# detector.net
KiCad netlist of a schematic drawn in EAGLE
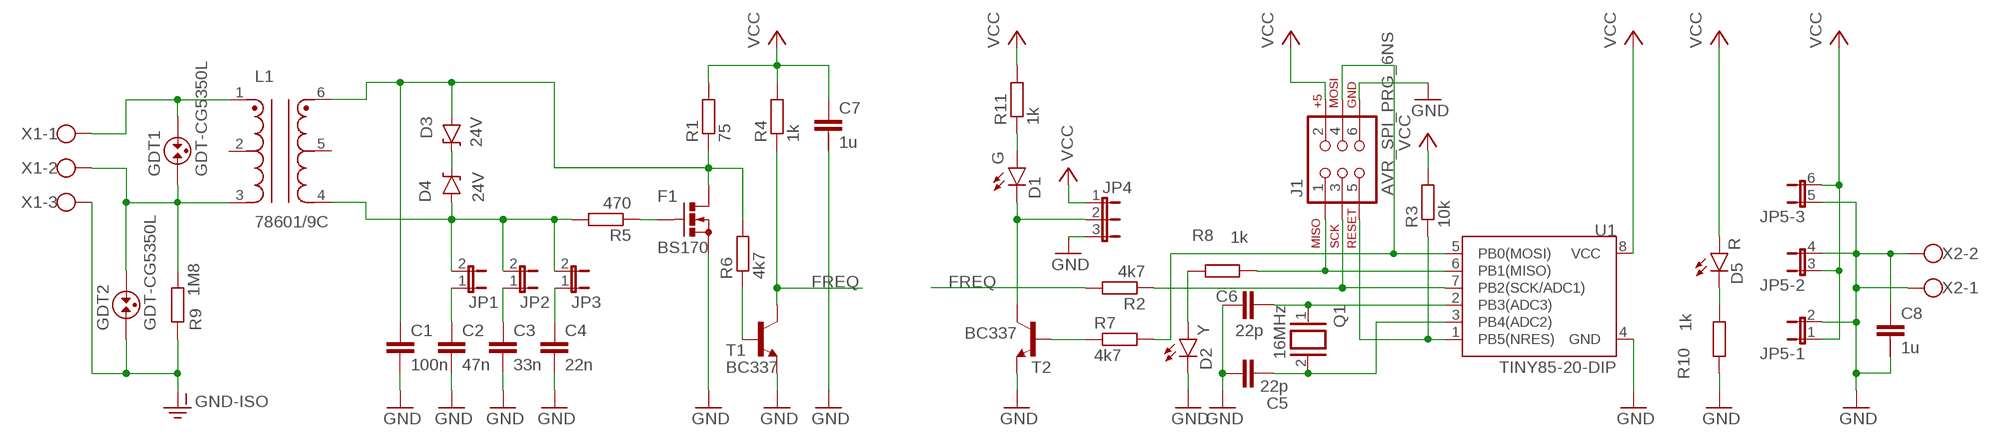
[diagram p0: schematic, sheet 1]

(export (version "E")
  (design (tool "Eeschema 10.0.6"))
  (components
    (comp (ref "C1")
      (value "100n")
      (footprint "eagle-import:C050-024X044")
      (libsource (lib "eagle-import") (part "C-EU050-024X044"))
    )
    (comp (ref "C2")
      (value "47n")
      (footprint "eagle-import:C050-024X044")
      (libsource (lib "eagle-import") (part "C-EU050-024X044"))
    )
    (comp (ref "C3")
      (value "33n")
      (footprint "eagle-import:C050-024X044")
      (libsource (lib "eagle-import") (part "C-EU050-024X044"))
    )
    (comp (ref "C4")
      (value "22n")
      (footprint "eagle-import:C050-024X044")
      (libsource (lib "eagle-import") (part "C-EU050-024X044"))
    )
    (comp (ref "C5")
      (value "22p")
      (footprint "eagle-import:C050-024X044")
      (libsource (lib "eagle-import") (part "C-EU050-024X044"))
    )
    (comp (ref "C6")
      (value "22p")
      (footprint "eagle-import:C050-024X044")
      (libsource (lib "eagle-import") (part "C-EU050-024X044"))
    )
    (comp (ref "C7")
      (value "1u")
      (footprint "eagle-import:C2.5_5-4")
      (libsource (lib "eagle-import") (part "C-2.5-5/4"))
    )
    (comp (ref "C8")
      (value "1u")
      (footprint "eagle-import:C2.5_5-4")
      (libsource (lib "eagle-import") (part "C-2.5-5/4"))
    )
    (comp (ref "D1")
      (value "G")
      (footprint "eagle-import:LED3MM")
      (libsource (lib "eagle-import") (part "LED3MM"))
    )
    (comp (ref "D2")
      (value "Y")
      (footprint "eagle-import:LED3MM")
      (libsource (lib "eagle-import") (part "LED3MM"))
    )
    (comp (ref "D3")
      (value "24V")
      (footprint "eagle-import:DIODE-BZT52")
      (libsource (lib "eagle-import") (part "DIODE-ZENER"))
    )
    (comp (ref "D4")
      (value "24V")
      (footprint "eagle-import:DIODE-BZT52")
      (libsource (lib "eagle-import") (part "DIODE-ZENER"))
    )
    (comp (ref "D5")
      (value "R")
      (footprint "eagle-import:LED3MM")
      (libsource (lib "eagle-import") (part "LED3MM"))
    )
    (comp (ref "F1")
      (value "BS170")
      (footprint "eagle-import:SOT54E")
      (libsource (lib "eagle-import") (part "BS170"))
    )
    (comp (ref "GDT1")
      (value "GDT-CG5350L")
      (footprint "eagle-import:CG5350L")
      (libsource (lib "eagle-import") (part "GDT-CG5350L"))
    )
    (comp (ref "GDT2")
      (value "GDT-CG5350L")
      (footprint "eagle-import:CG5350L")
      (libsource (lib "eagle-import") (part "GDT-CG5350L"))
    )
    (comp (ref "J1")
      (value "AVR_SPI_PRG_6NS")
      (footprint "eagle-import:2X3-NS")
      (libsource (lib "eagle-import") (part "AVR_SPI_PRG_6NS"))
    )
    (comp (ref "JP1")
      (value "JUMPER-2PTH")
      (footprint "eagle-import:1X02")
      (libsource (lib "eagle-import") (part "JUMPER-2PTH"))
    )
    (comp (ref "JP2")
      (value "JUMPER-2PTH")
      (footprint "eagle-import:1X02")
      (libsource (lib "eagle-import") (part "JUMPER-2PTH"))
    )
    (comp (ref "JP3")
      (value "JUMPER-2PTH")
      (footprint "eagle-import:1X02")
      (libsource (lib "eagle-import") (part "JUMPER-2PTH"))
    )
    (comp (ref "JP4")
      (value "JP2E")
      (footprint "eagle-import:JP2")
      (libsource (lib "eagle-import") (part "JP2E"))
    )
    (comp (ref "JP5")
      (value "JP3QE")
      (footprint "eagle-import:JP3Q")
      (libsource (lib "eagle-import") (part "JP3QE"))
    )
    (comp (ref "L1")
      (value "78601/9C")
      (footprint "eagle-import:78601_9C")
      (libsource (lib "eagle-import") (part "78601/9C"))
    )
    (comp (ref "Q1")
      (value "16MHz")
      (footprint "eagle-import:QS")
      (libsource (lib "eagle-import") (part "XTAL/S"))
    )
    (comp (ref "R1")
      (value "75")
      (footprint "eagle-import:0204_7")
      (libsource (lib "eagle-import") (part "R-EU_0204/7"))
    )
    (comp (ref "R2")
      (value "4k7")
      (footprint "eagle-import:0204_5")
      (libsource (lib "eagle-import") (part "R-EU_0204/5"))
    )
    (comp (ref "R3")
      (value "10k")
      (footprint "eagle-import:0204_5")
      (libsource (lib "eagle-import") (part "R-EU_0204/5"))
    )
    (comp (ref "R4")
      (value "1k")
      (footprint "eagle-import:0204_5")
      (libsource (lib "eagle-import") (part "R-EU_0204/5"))
    )
    (comp (ref "R5")
      (value "470")
      (footprint "eagle-import:0204_5")
      (libsource (lib "eagle-import") (part "R-EU_0204/5"))
    )
    (comp (ref "R6")
      (value "4k7")
      (footprint "eagle-import:0204_5")
      (libsource (lib "eagle-import") (part "R-EU_0204/5"))
    )
    (comp (ref "R7")
      (value "4k7")
      (footprint "eagle-import:0204_5")
      (libsource (lib "eagle-import") (part "R-EU_0204/5"))
    )
    (comp (ref "R8")
      (value "1k")
      (footprint "eagle-import:0204_5")
      (libsource (lib "eagle-import") (part "R-EU_0204/5"))
    )
    (comp (ref "R9")
      (value "1M8")
      (footprint "eagle-import:0204_5")
      (libsource (lib "eagle-import") (part "R-EU_0204/5"))
    )
    (comp (ref "R10")
      (value "1k")
      (footprint "eagle-import:0204_5")
      (libsource (lib "eagle-import") (part "R-EU_0204/5"))
    )
    (comp (ref "R11")
      (value "1k")
      (footprint "eagle-import:0204_5")
      (libsource (lib "eagle-import") (part "R-EU_0204/5"))
    )
    (comp (ref "T1")
      (value "BC337")
      (footprint "eagle-import:TO92-CBE")
      (libsource (lib "eagle-import") (part "-NPN-TO92-CBEBC337"))
    )
    (comp (ref "T2")
      (value "BC337")
      (footprint "eagle-import:TO92-CBE")
      (libsource (lib "eagle-import") (part "-NPN-TO92-CBEBC337"))
    )
    (comp (ref "U1")
      (value "TINY85-20-DIP")
      (footprint "eagle-import:DIP08")
      (libsource (lib "eagle-import") (part "ATTINY45TINY45-20-DIP"))
    )
    (comp (ref "X1")
      (value "W237-103")
      (footprint "eagle-import:W237-103")
      (fields (field (name "MPN") "237-103"))
      (libsource (lib "eagle-import") (part "W237-103"))
    )
    (comp (ref "X2")
      (value "W237-102")
      (footprint "eagle-import:W237-102")
      (fields (field (name "MPN") "237-102"))
      (libsource (lib "eagle-import") (part "W237-102"))
    )
  )
  (nets
    (net (code "1") (name "/FREQ") (class "Default")
      (node (ref "R2") (pin "2") (pinfunction "2_2") (pintype "passive"))
      (node (ref "R4") (pin "1") (pinfunction "1_1") (pintype "passive"))
      (node (ref "T1") (pin "C") (pinfunction "C_C") (pintype "passive"))
    )
    (net (code "2") (name "GND") (class "Default")
      (node (ref "C1") (pin "2") (pinfunction "2_2") (pintype "passive"))
      (node (ref "C2") (pin "2") (pinfunction "2_2") (pintype "passive"))
      (node (ref "C3") (pin "2") (pinfunction "2_2") (pintype "passive"))
      (node (ref "C4") (pin "2") (pinfunction "2_2") (pintype "passive"))
      (node (ref "C5") (pin "1") (pinfunction "1_1") (pintype "passive"))
      (node (ref "C6") (pin "1") (pinfunction "1_1") (pintype "passive"))
      (node (ref "C7") (pin "2") (pinfunction "2_2") (pintype "passive"))
      (node (ref "C8") (pin "1") (pinfunction "1_1") (pintype "passive"))
      (node (ref "C8") (pin "2") (pinfunction "2_2") (pintype "passive"))
      (node (ref "D2") (pin "K") (pinfunction "C_K") (pintype "passive"))
      (node (ref "F1") (pin "S") (pinfunction "S_S") (pintype "passive"))
      (node (ref "J1") (pin "6") (pinfunction "6_6") (pintype "passive"))
      (node (ref "JP4") (pin "3") (pinfunction "3_3") (pintype "passive"))
      (node (ref "JP5") (pin "2") (pinfunction "2_2") (pintype "passive"))
      (node (ref "JP5") (pin "4") (pinfunction "2_4") (pintype "passive"))
      (node (ref "JP5") (pin "5") (pinfunction "1_5") (pintype "passive"))
      (node (ref "R10") (pin "2") (pinfunction "2_2") (pintype "passive"))
      (node (ref "T1") (pin "E") (pinfunction "E_E") (pintype "passive"))
      (node (ref "T2") (pin "E") (pinfunction "E_E") (pintype "passive"))
      (node (ref "U1") (pin "4") (pinfunction "GND_4") (pintype "bidirectional"))
      (node (ref "X2") (pin "1") (pinfunction "KL_1") (pintype "passive"))
      (node (ref "X2") (pin "2") (pinfunction "KL_2") (pintype "passive"))
    )
    (net (code "3") (name "GND-ISO") (class "Default")
      (node (ref "GDT2") (pin "1") (pinfunction "1_1") (pintype "passive"))
      (node (ref "R9") (pin "1") (pinfunction "1_1") (pintype "passive"))
      (node (ref "X1") (pin "3") (pinfunction "KL_3") (pintype "passive"))
    )
    (net (code "4") (name "Net-(C1-Pad1)") (class "Default")
      (node (ref "C1") (pin "1") (pinfunction "1_1") (pintype "passive"))
      (node (ref "D3") (pin "A") (pinfunction "A_A") (pintype "passive"))
      (node (ref "F1") (pin "D") (pinfunction "D_D") (pintype "passive"))
      (node (ref "L1") (pin "6") (pinfunction "6_6") (pintype "passive"))
      (node (ref "R1") (pin "1") (pinfunction "1_1") (pintype "passive"))
      (node (ref "R6") (pin "2") (pinfunction "2_2") (pintype "passive"))
    )
    (net (code "5") (name "Net-(C2-Pad1)") (class "Default")
      (node (ref "C2") (pin "1") (pinfunction "1_1") (pintype "passive"))
      (node (ref "JP1") (pin "1") (pinfunction "1_1") (pintype "passive"))
    )
    (net (code "6") (name "Net-(C3-Pad1)") (class "Default")
      (node (ref "C3") (pin "1") (pinfunction "1_1") (pintype "passive"))
      (node (ref "JP2") (pin "1") (pinfunction "1_1") (pintype "passive"))
    )
    (net (code "7") (name "Net-(C4-Pad1)") (class "Default")
      (node (ref "C4") (pin "1") (pinfunction "1_1") (pintype "passive"))
      (node (ref "JP3") (pin "1") (pinfunction "1_1") (pintype "passive"))
    )
    (net (code "8") (name "Net-(D1-C)") (class "Default")
      (node (ref "D1") (pin "K") (pinfunction "C_K") (pintype "passive"))
      (node (ref "JP4") (pin "2") (pinfunction "2_2") (pintype "passive"))
      (node (ref "T2") (pin "C") (pinfunction "C_C") (pintype "passive"))
    )
    (net (code "9") (name "Net-(D1-PadA)") (class "Default")
      (node (ref "D1") (pin "A") (pinfunction "A_A") (pintype "passive"))
      (node (ref "R11") (pin "1") (pinfunction "1_1") (pintype "passive"))
    )
    (net (code "10") (name "Net-(D2-PadA)") (class "Default")
      (node (ref "D2") (pin "A") (pinfunction "A_A") (pintype "passive"))
      (node (ref "R8") (pin "2") (pinfunction "2_2") (pintype "passive"))
    )
    (net (code "11") (name "Net-(D3-PadC)") (class "Default")
      (node (ref "D3") (pin "C") (pinfunction "C_C") (pintype "passive"))
      (node (ref "D4") (pin "C") (pinfunction "C_C") (pintype "passive"))
    )
    (net (code "12") (name "Net-(D4-PadA)") (class "Default")
      (node (ref "D4") (pin "A") (pinfunction "A_A") (pintype "passive"))
      (node (ref "JP1") (pin "2") (pinfunction "2_2") (pintype "passive"))
      (node (ref "JP2") (pin "2") (pinfunction "2_2") (pintype "passive"))
      (node (ref "JP3") (pin "2") (pinfunction "2_2") (pintype "passive"))
      (node (ref "L1") (pin "4") (pinfunction "4_4") (pintype "passive"))
      (node (ref "R5") (pin "2") (pinfunction "2_2") (pintype "passive"))
    )
    (net (code "13") (name "Net-(D5-C)") (class "Default")
      (node (ref "D5") (pin "K") (pinfunction "C_K") (pintype "passive"))
      (node (ref "R10") (pin "1") (pinfunction "1_1") (pintype "passive"))
    )
    (net (code "14") (name "Net-(F1-PadG)") (class "Default")
      (node (ref "F1") (pin "G") (pinfunction "G_G") (pintype "passive"))
      (node (ref "R5") (pin "1") (pinfunction "1_1") (pintype "passive"))
    )
    (net (code "15") (name "Net-(R6-Pad1)") (class "Default")
      (node (ref "R6") (pin "1") (pinfunction "1_1") (pintype "passive"))
      (node (ref "T1") (pin "B") (pinfunction "B_B") (pintype "passive"))
    )
    (net (code "16") (name "Net-(R7-Pad1)") (class "Default")
      (node (ref "R7") (pin "1") (pinfunction "1_1") (pintype "passive"))
      (node (ref "T2") (pin "B") (pinfunction "B_B") (pintype "passive"))
    )
    (net (code "17") (name "Net-(U1-PB0(MOSI))") (class "Default")
      (node (ref "J1") (pin "4") (pinfunction "4_4") (pintype "passive"))
      (node (ref "R7") (pin "2") (pinfunction "2_2") (pintype "passive"))
      (node (ref "U1") (pin "5") (pinfunction "PB0(MOSI)_5") (pintype "bidirectional"))
    )
    (net (code "18") (name "Net-(U1-PB1(MISO))") (class "Default")
      (node (ref "J1") (pin "1") (pinfunction "1_1") (pintype "passive"))
      (node (ref "R8") (pin "1") (pinfunction "1_1") (pintype "passive"))
      (node (ref "U1") (pin "6") (pinfunction "PB1(MISO)_6") (pintype "bidirectional"))
    )
    (net (code "19") (name "Net-(U1-PB2(SCK{slash}ADC1))") (class "Default")
      (node (ref "J1") (pin "3") (pinfunction "3_3") (pintype "passive"))
      (node (ref "R2") (pin "1") (pinfunction "1_1") (pintype "passive"))
      (node (ref "U1") (pin "7") (pinfunction "PB2(SCK/ADC1)_7") (pintype "bidirectional"))
    )
    (net (code "20") (name "Net-(U1-PB3(ADC3))") (class "Default")
      (node (ref "C6") (pin "2") (pinfunction "2_2") (pintype "passive"))
      (node (ref "Q1") (pin "1") (pinfunction "1_1") (pintype "passive"))
      (node (ref "U1") (pin "2") (pinfunction "PB3(ADC3)_2") (pintype "bidirectional"))
    )
    (net (code "21") (name "Net-(U1-PB4(ADC2))") (class "Default")
      (node (ref "C5") (pin "2") (pinfunction "2_2") (pintype "passive"))
      (node (ref "Q1") (pin "2") (pinfunction "2_2") (pintype "passive"))
      (node (ref "U1") (pin "3") (pinfunction "PB4(ADC2)_3") (pintype "bidirectional"))
    )
    (net (code "22") (name "Net-(U1-PB5(NRES))") (class "Default")
      (node (ref "J1") (pin "5") (pinfunction "5_5") (pintype "passive"))
      (node (ref "R3") (pin "1") (pinfunction "1_1") (pintype "passive"))
      (node (ref "U1") (pin "1") (pinfunction "PB5(NRES)_1") (pintype "bidirectional"))
    )
    (net (code "23") (name "Net-(X1A-KL)") (class "Default")
      (node (ref "GDT1") (pin "2") (pinfunction "2_2") (pintype "passive"))
      (node (ref "L1") (pin "1") (pinfunction "1_1") (pintype "passive"))
      (node (ref "X1") (pin "1") (pinfunction "KL_1") (pintype "passive"))
    )
    (net (code "24") (name "Net-(X1B-KL)") (class "Default")
      (node (ref "GDT1") (pin "1") (pinfunction "1_1") (pintype "passive"))
      (node (ref "GDT2") (pin "2") (pinfunction "2_2") (pintype "passive"))
      (node (ref "L1") (pin "3") (pinfunction "3_3") (pintype "passive"))
      (node (ref "R9") (pin "2") (pinfunction "2_2") (pintype "passive"))
      (node (ref "X1") (pin "2") (pinfunction "KL_2") (pintype "passive"))
    )
    (net (code "25") (name "VCC") (class "Default")
      (node (ref "C7") (pin "1") (pinfunction "1_1") (pintype "passive"))
      (node (ref "D5") (pin "A") (pinfunction "A_A") (pintype "passive"))
      (node (ref "J1") (pin "2") (pinfunction "2_2") (pintype "passive"))
      (node (ref "JP4") (pin "1") (pinfunction "1_1") (pintype "passive"))
      (node (ref "JP5") (pin "1") (pinfunction "1_1") (pintype "passive"))
      (node (ref "JP5") (pin "3") (pinfunction "1_3") (pintype "passive"))
      (node (ref "JP5") (pin "6") (pinfunction "2_6") (pintype "passive"))
      (node (ref "R1") (pin "2") (pinfunction "2_2") (pintype "passive"))
      (node (ref "R11") (pin "2") (pinfunction "2_2") (pintype "passive"))
      (node (ref "R3") (pin "2") (pinfunction "2_2") (pintype "passive"))
      (node (ref "R4") (pin "2") (pinfunction "2_2") (pintype "passive"))
      (node (ref "U1") (pin "8") (pinfunction "VCC_8") (pintype "bidirectional"))
    )
    (net (code "26") (name "unconnected-(C7-Pad3)") (class "Default")
      (node (ref "C7") (pin "3") (pinfunction "3_3") (pintype "passive"))
    )
    (net (code "27") (name "unconnected-(C8-Pad3)") (class "Default")
      (node (ref "C8") (pin "3") (pinfunction "3_3") (pintype "passive"))
    )
    (net (code "28") (name "unconnected-(L1-Pad2)") (class "Default")
      (node (ref "L1") (pin "2") (pinfunction "2_2") (pintype "passive"))
    )
    (net (code "29") (name "unconnected-(L1-Pad5)") (class "Default")
      (node (ref "L1") (pin "5") (pinfunction "5_5") (pintype "passive"))
    )
  )
)
